# 13_B_T_B_IO.net
KiCad netlist of a schematic drawn in Altium Designer
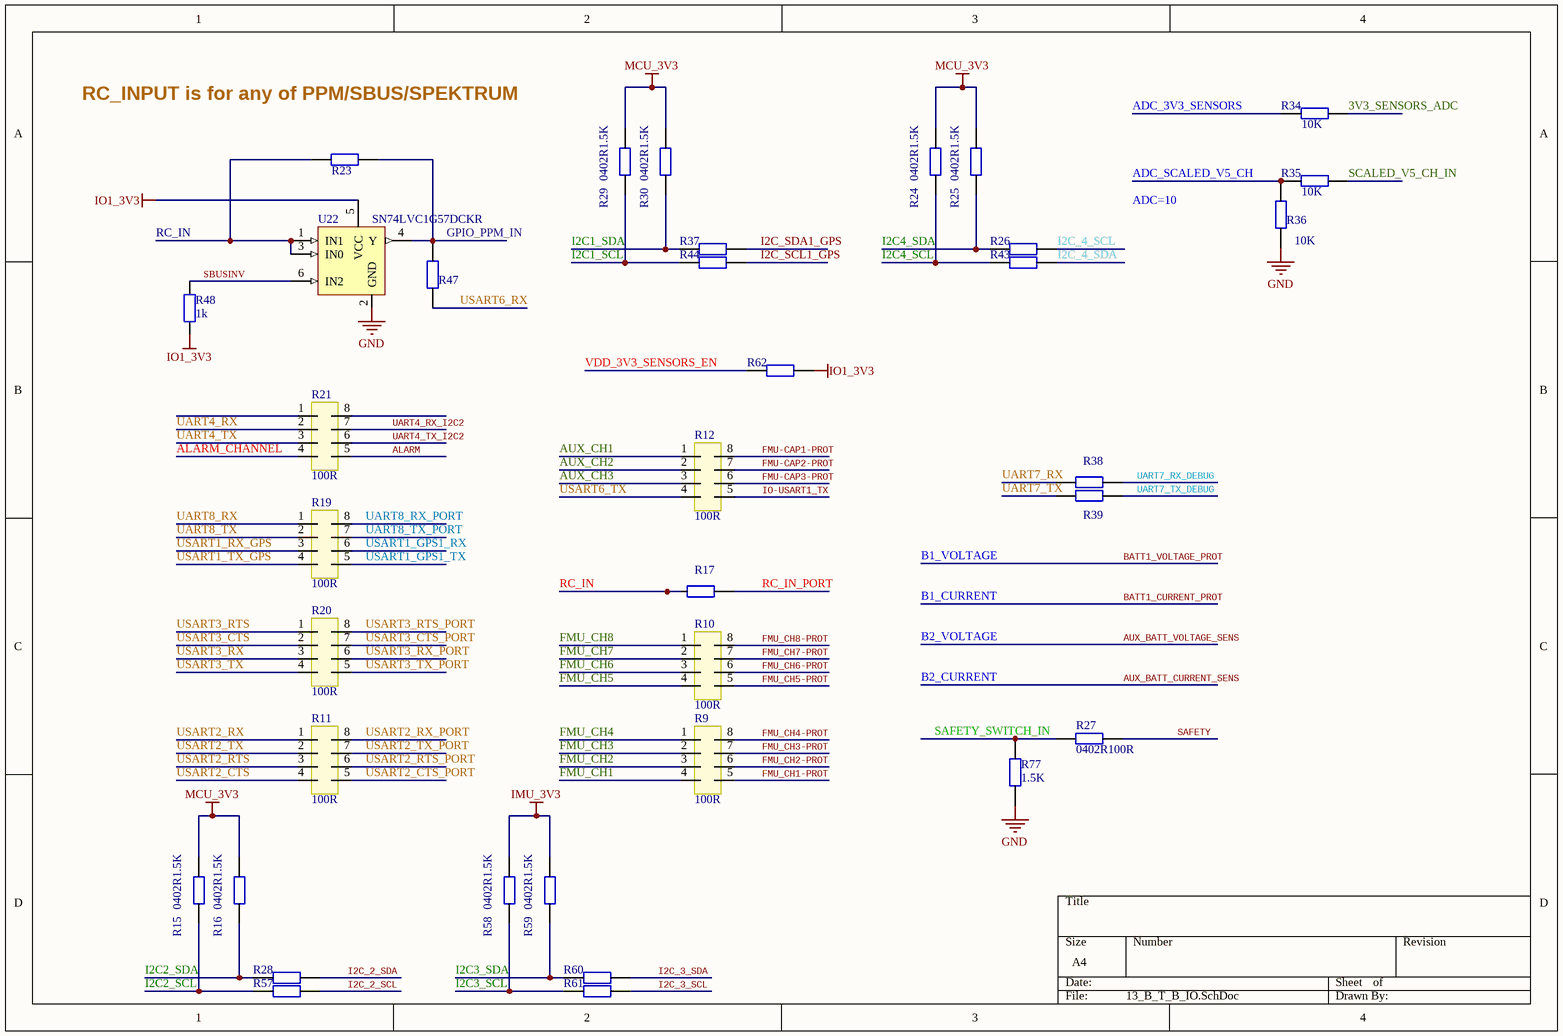
[diagram p0: 13_B_T_B_IO.SchDoc]

(export (version "E")
  (design (tool "Eeschema 10.0.6"))
  (components
    (comp (ref "R9") (value "100R") (footprint "0402_4r") (libsource (lib "CUAV") (part "0402-8R-4R")))
    (comp (ref "R10") (value "100R") (footprint "0402_4r") (libsource (lib "CUAV") (part "0402-8R-4R")))
    (comp (ref "R11") (value "100R") (footprint "0402_4r") (libsource (lib "CUAV") (part "0402-8R-4R")))
    (comp (ref "R12") (value "100R") (footprint "0402_4r") (libsource (lib "CUAV") (part "0402-8R-4R")))
    (comp (ref "R15")
      (value "0402R1.5K")
      (footprint "0402R")
      (description "0402R10K 1%")
      (libsource (lib "CUAV") (part "0402R10K"))
    )
    (comp (ref "R16")
      (value "0402R1.5K")
      (footprint "0402R")
      (description "0402R10K 1%")
      (libsource (lib "CUAV") (part "0402R10K"))
    )
    (comp (ref "R17")
      (value "0402R100R")
      (footprint "0402R")
      (description "0402R100R 1%")
      (libsource (lib "CUAV") (part "0402R100R"))
    )
    (comp (ref "R19") (value "100R") (footprint "0402_4r") (libsource (lib "CUAV") (part "0402-8R-4R")))
    (comp (ref "R20") (value "100R") (footprint "0402_4r") (libsource (lib "CUAV") (part "0402-8R-4R")))
    (comp (ref "R21") (value "100R") (footprint "0402_4r") (libsource (lib "CUAV") (part "0402-8R-4R")))
    (comp (ref "R23")
      (value "100R/NC")
      (footprint "0402R")
      (description "0402R100R 1%")
      (libsource (lib "") (part "0402R100R_1"))
    )
    (comp (ref "R24")
      (value "0402R1.5K")
      (footprint "0402R")
      (description "0402R10K 1%")
      (libsource (lib "CUAV") (part "0402R10K"))
    )
    (comp (ref "R25")
      (value "0402R1.5K")
      (footprint "0402R")
      (description "0402R10K 1%")
      (libsource (lib "CUAV") (part "0402R10K"))
    )
    (comp (ref "R26")
      (value "0402R100R")
      (footprint "0402R")
      (description "0402R100R 1%")
      (libsource (lib "CUAV") (part "0402R100R"))
    )
    (comp (ref "R27")
      (value "0402R100R")
      (footprint "0402R")
      (description "0402R100R 1%")
      (libsource (lib "CUAV") (part "0402R100R"))
    )
    (comp (ref "R28")
      (value "0402R100R")
      (footprint "0402R")
      (description "0402R100R 1%")
      (libsource (lib "CUAV") (part "0402R100R"))
    )
    (comp (ref "R29")
      (value "0402R1.5K")
      (footprint "0402R")
      (description "0402R10K 1%")
      (libsource (lib "CUAV") (part "0402R10K"))
    )
    (comp (ref "R30")
      (value "0402R1.5K")
      (footprint "0402R")
      (description "0402R10K 1%")
      (libsource (lib "CUAV") (part "0402R10K"))
    )
    (comp (ref "R34")
      (value "10K")
      (footprint "0402R")
      (description "0402R100R 1%")
      (libsource (lib "CUAV") (part "0402R100R"))
    )
    (comp (ref "R35")
      (value "10K")
      (footprint "0402R")
      (description "0402R100R 1%")
      (libsource (lib "CUAV") (part "0402R100R"))
    )
    (comp (ref "R36")
      (value "10K")
      (footprint "0402R")
      (description "0402R100R 1%")
      (libsource (lib "") (part "0402R100R_2"))
    )
    (comp (ref "R37")
      (value "0402R100R")
      (footprint "0402R")
      (description "0402R100R 1%")
      (libsource (lib "CUAV") (part "0402R100R"))
    )
    (comp (ref "R38")
      (value "0402R100R")
      (footprint "0402R")
      (description "0402R100R 1%")
      (libsource (lib "CUAV") (part "0402R100R"))
    )
    (comp (ref "R39")
      (value "0402R100R")
      (footprint "0402R")
      (description "0402R100R 1%")
      (libsource (lib "CUAV") (part "0402R100R"))
    )
    (comp (ref "R43")
      (value "0402R100R")
      (footprint "0402R")
      (description "0402R100R 1%")
      (libsource (lib "CUAV") (part "0402R100R"))
    )
    (comp (ref "R44")
      (value "0402R100R")
      (footprint "0402R")
      (description "0402R100R 1%")
      (libsource (lib "CUAV") (part "0402R100R"))
    )
    (comp (ref "R47")
      (value "100R")
      (footprint "0402R")
      (description "0402R100R 1%")
      (libsource (lib "") (part "0402R100R_2"))
    )
    (comp (ref "R48")
      (value "1k")
      (description "Resistor")
      (fields (field (name "PUBLISHER") "Altium Limited"))
      (libsource (lib "Miscellaneous Devices") (part "Res2"))
    )
    (comp (ref "R57")
      (value "0402R100R")
      (footprint "0402R")
      (description "0402R100R 1%")
      (libsource (lib "CUAV") (part "0402R100R"))
    )
    (comp (ref "R58")
      (value "0402R1.5K")
      (footprint "0402R")
      (description "0402R10K 1%")
      (libsource (lib "CUAV") (part "0402R10K"))
    )
    (comp (ref "R59")
      (value "0402R1.5K")
      (footprint "0402R")
      (description "0402R10K 1%")
      (libsource (lib "CUAV") (part "0402R10K"))
    )
    (comp (ref "R60")
      (value "0402R100R")
      (footprint "0402R")
      (description "0402R100R 1%")
      (libsource (lib "CUAV") (part "0402R100R"))
    )
    (comp (ref "R61")
      (value "0402R100R")
      (footprint "0402R")
      (description "0402R100R 1%")
      (libsource (lib "CUAV") (part "0402R100R"))
    )
    (comp (ref "R62")
      (value "10K/NC")
      (footprint "0402R")
      (description "0402R100R 1%")
      (libsource (lib "CUAV") (part "0402R100R"))
    )
    (comp (ref "R77")
      (value "1.5K")
      (footprint "0402R")
      (description "0402R100R 1%")
      (libsource (lib "") (part "0402R100R_2"))
    )
    (comp (ref "U22")
      (value "SN74LVC1G57DCKR")
      (footprint "sot323-6")
      (libsource (lib "My_Altium") (part "74LVC1G57"))
    )
  )
  (nets
    (net (code "1") (name "/3V3_SENSORS_ADC") (class "Default")
      (node (ref "R34") (pin "2") (pintype "passive"))
    )
    (net (code "3") (name "/ADC_3V3_SENSORS") (class "Default")
      (node (ref "R34") (pin "1") (pintype "passive"))
    )
    (net (code "4") (name "/ADC_SCALED_V5_CH") (class "Default")
      (node (ref "R35") (pin "1") (pintype "passive"))
      (node (ref "R36") (pin "2") (pintype "passive"))
    )
    (net (code "5") (name "/ALARM") (class "Default")
      (node (ref "R21") (pin "5") (pinfunction "5_5") (pintype "passive"))
    )
    (net (code "6") (name "/ALARM_CHANNEL") (class "Default")
      (node (ref "R21") (pin "4") (pinfunction "4_4") (pintype "passive"))
    )
    (net (code "9") (name "/AUX_CH1") (class "Default")
      (node (ref "R12") (pin "1") (pinfunction "1_1") (pintype "passive"))
    )
    (net (code "10") (name "/AUX_CH2") (class "Default")
      (node (ref "R12") (pin "2") (pinfunction "2_2") (pintype "passive"))
    )
    (net (code "11") (name "/AUX_CH3") (class "Default")
      (node (ref "R12") (pin "3") (pinfunction "3_3") (pintype "passive"))
    )
    (net (code "14") (name "/FMU-CAP1-PROT") (class "Default")
      (node (ref "R12") (pin "8") (pinfunction "8_8") (pintype "passive"))
    )
    (net (code "15") (name "/FMU-CAP2-PROT") (class "Default")
      (node (ref "R12") (pin "7") (pinfunction "7_7") (pintype "passive"))
    )
    (net (code "16") (name "/FMU-CAP3-PROT") (class "Default")
      (node (ref "R12") (pin "6") (pinfunction "6_6") (pintype "passive"))
    )
    (net (code "17") (name "/FMU_CH1") (class "Default")
      (node (ref "R9") (pin "4") (pinfunction "4_4") (pintype "passive"))
    )
    (net (code "18") (name "/FMU_CH1-PROT") (class "Default")
      (node (ref "R9") (pin "5") (pinfunction "5_5") (pintype "passive"))
    )
    (net (code "19") (name "/FMU_CH2") (class "Default")
      (node (ref "R9") (pin "3") (pinfunction "3_3") (pintype "passive"))
    )
    (net (code "20") (name "/FMU_CH2-PROT") (class "Default")
      (node (ref "R9") (pin "6") (pinfunction "6_6") (pintype "passive"))
    )
    (net (code "21") (name "/FMU_CH3") (class "Default")
      (node (ref "R9") (pin "2") (pinfunction "2_2") (pintype "passive"))
    )
    (net (code "22") (name "/FMU_CH3-PROT") (class "Default")
      (node (ref "R9") (pin "7") (pinfunction "7_7") (pintype "passive"))
    )
    (net (code "23") (name "/FMU_CH4") (class "Default")
      (node (ref "R9") (pin "1") (pinfunction "1_1") (pintype "passive"))
    )
    (net (code "24") (name "/FMU_CH4-PROT") (class "Default")
      (node (ref "R9") (pin "8") (pinfunction "8_8") (pintype "passive"))
    )
    (net (code "25") (name "/FMU_CH5") (class "Default")
      (node (ref "R10") (pin "4") (pinfunction "4_4") (pintype "passive"))
    )
    (net (code "26") (name "/FMU_CH5-PROT") (class "Default")
      (node (ref "R10") (pin "5") (pinfunction "5_5") (pintype "passive"))
    )
    (net (code "27") (name "/FMU_CH6") (class "Default")
      (node (ref "R10") (pin "3") (pinfunction "3_3") (pintype "passive"))
    )
    (net (code "28") (name "/FMU_CH6-PROT") (class "Default")
      (node (ref "R10") (pin "6") (pinfunction "6_6") (pintype "passive"))
    )
    (net (code "29") (name "/FMU_CH7") (class "Default")
      (node (ref "R10") (pin "2") (pinfunction "2_2") (pintype "passive"))
    )
    (net (code "30") (name "/FMU_CH7-PROT") (class "Default")
      (node (ref "R10") (pin "7") (pinfunction "7_7") (pintype "passive"))
    )
    (net (code "31") (name "/FMU_CH8") (class "Default")
      (node (ref "R10") (pin "1") (pinfunction "1_1") (pintype "passive"))
    )
    (net (code "32") (name "/FMU_CH8-PROT") (class "Default")
      (node (ref "R10") (pin "8") (pinfunction "8_8") (pintype "passive"))
    )
    (net (code "33") (name "/GPIO_PPM_IN") (class "Default")
      (node (ref "R23") (pin "1") (pintype "passive"))
      (node (ref "R47") (pin "2") (pintype "passive"))
      (node (ref "U22") (pin "4") (pinfunction "Y_4") (pintype "output"))
    )
    (net (code "34") (name "/I2C1_SCL") (class "Default")
      (node (ref "R29") (pin "1") (pintype "passive"))
      (node (ref "R44") (pin "1") (pintype "passive"))
    )
    (net (code "35") (name "/I2C1_SDA") (class "Default")
      (node (ref "R30") (pin "1") (pintype "passive"))
      (node (ref "R37") (pin "1") (pintype "passive"))
    )
    (net (code "36") (name "/I2C2_SCL") (class "Default")
      (node (ref "R15") (pin "1") (pintype "passive"))
      (node (ref "R57") (pin "1") (pintype "passive"))
    )
    (net (code "37") (name "/I2C2_SDA") (class "Default")
      (node (ref "R16") (pin "1") (pintype "passive"))
      (node (ref "R28") (pin "1") (pintype "passive"))
    )
    (net (code "38") (name "/I2C3_SCL") (class "Default")
      (node (ref "R58") (pin "1") (pintype "passive"))
      (node (ref "R61") (pin "1") (pintype "passive"))
    )
    (net (code "39") (name "/I2C3_SDA") (class "Default")
      (node (ref "R59") (pin "1") (pintype "passive"))
      (node (ref "R60") (pin "1") (pintype "passive"))
    )
    (net (code "40") (name "/I2C4_SCL") (class "Default")
      (node (ref "R24") (pin "1") (pintype "passive"))
      (node (ref "R43") (pin "1") (pintype "passive"))
    )
    (net (code "41") (name "/I2C4_SDA") (class "Default")
      (node (ref "R25") (pin "1") (pintype "passive"))
      (node (ref "R26") (pin "1") (pintype "passive"))
    )
    (net (code "42") (name "/I2C_2_SCL") (class "Default") (node (ref "R57") (pin "2") (pintype "passive")))
    (net (code "43") (name "/I2C_2_SDA") (class "Default") (node (ref "R28") (pin "2") (pintype "passive")))
    (net (code "44") (name "/I2C_3_SCL") (class "Default") (node (ref "R61") (pin "2") (pintype "passive")))
    (net (code "45") (name "/I2C_3_SDA") (class "Default") (node (ref "R60") (pin "2") (pintype "passive")))
    (net (code "46") (name "/I2C_4_SCL") (class "Default") (node (ref "R26") (pin "2") (pintype "passive")))
    (net (code "47") (name "/I2C_4_SDA") (class "Default") (node (ref "R43") (pin "2") (pintype "passive")))
    (net (code "48") (name "/I2C_SCL1_GPS") (class "Default")
      (node (ref "R44") (pin "2") (pintype "passive"))
    )
    (net (code "49") (name "/I2C_SDA1_GPS") (class "Default")
      (node (ref "R37") (pin "2") (pintype "passive"))
    )
    (net (code "50") (name "/IO-USART1_TX") (class "Default")
      (node (ref "R12") (pin "5") (pinfunction "5_5") (pintype "passive"))
    )
    (net (code "51") (name "/RC_IN") (class "Default")
      (node (ref "R17") (pin "1") (pintype "passive"))
      (node (ref "R23") (pin "2") (pintype "passive"))
      (node (ref "U22") (pin "1") (pinfunction "IN1_1") (pintype "input"))
      (node (ref "U22") (pin "3") (pinfunction "IN0_3") (pintype "input"))
    )
    (net (code "52") (name "/RC_IN_PORT") (class "Default") (node (ref "R17") (pin "2") (pintype "passive")))
    (net (code "53") (name "/SAFETY") (class "Default") (node (ref "R27") (pin "2") (pintype "passive")))
    (net (code "54") (name "/SAFETY_SWITCH_IN") (class "Default")
      (node (ref "R27") (pin "1") (pintype "passive"))
      (node (ref "R77") (pin "2") (pintype "passive"))
    )
    (net (code "55") (name "/SBUSINV") (class "Default")
      (node (ref "R48") (pin "2") (pinfunction "2_2") (pintype "passive"))
      (node (ref "U22") (pin "6") (pinfunction "IN2_6") (pintype "input"))
    )
    (net (code "56") (name "/SCALED_V5_CH_IN") (class "Default")
      (node (ref "R35") (pin "2") (pintype "passive"))
    )
    (net (code "57") (name "/UART4_RX") (class "Default")
      (node (ref "R21") (pin "2") (pinfunction "2_2") (pintype "passive"))
    )
    (net (code "58") (name "/UART4_RX_I2C2") (class "Default")
      (node (ref "R21") (pin "7") (pinfunction "7_7") (pintype "passive"))
    )
    (net (code "59") (name "/UART4_TX") (class "Default")
      (node (ref "R21") (pin "3") (pinfunction "3_3") (pintype "passive"))
    )
    (net (code "60") (name "/UART4_TX_I2C2") (class "Default")
      (node (ref "R21") (pin "6") (pinfunction "6_6") (pintype "passive"))
    )
    (net (code "61") (name "/UART7_RX") (class "Default") (node (ref "R38") (pin "1") (pintype "passive")))
    (net (code "62") (name "/UART7_RX_DEBUG") (class "Default")
      (node (ref "R38") (pin "2") (pintype "passive"))
    )
    (net (code "63") (name "/UART7_TX") (class "Default") (node (ref "R39") (pin "1") (pintype "passive")))
    (net (code "64") (name "/UART7_TX_DEBUG") (class "Default")
      (node (ref "R39") (pin "2") (pintype "passive"))
    )
    (net (code "65") (name "/UART8_RX") (class "Default")
      (node (ref "R19") (pin "1") (pinfunction "1_1") (pintype "passive"))
    )
    (net (code "66") (name "/UART8_RX_PORT") (class "Default")
      (node (ref "R19") (pin "8") (pinfunction "8_8") (pintype "passive"))
    )
    (net (code "67") (name "/UART8_TX") (class "Default")
      (node (ref "R19") (pin "2") (pinfunction "2_2") (pintype "passive"))
    )
    (net (code "68") (name "/UART8_TX_PORT") (class "Default")
      (node (ref "R19") (pin "7") (pinfunction "7_7") (pintype "passive"))
    )
    (net (code "69") (name "/USART1_GPS1_RX") (class "Default")
      (node (ref "R19") (pin "6") (pinfunction "6_6") (pintype "passive"))
    )
    (net (code "70") (name "/USART1_GPS1_TX") (class "Default")
      (node (ref "R19") (pin "5") (pinfunction "5_5") (pintype "passive"))
    )
    (net (code "71") (name "/USART1_RX_GPS") (class "Default")
      (node (ref "R19") (pin "3") (pinfunction "3_3") (pintype "passive"))
    )
    (net (code "72") (name "/USART1_TX_GPS") (class "Default")
      (node (ref "R19") (pin "4") (pinfunction "4_4") (pintype "passive"))
    )
    (net (code "73") (name "/USART2_CTS") (class "Default")
      (node (ref "R11") (pin "4") (pinfunction "4_4") (pintype "passive"))
    )
    (net (code "74") (name "/USART2_CTS_PORT") (class "Default")
      (node (ref "R11") (pin "5") (pinfunction "5_5") (pintype "passive"))
    )
    (net (code "75") (name "/USART2_RTS") (class "Default")
      (node (ref "R11") (pin "3") (pinfunction "3_3") (pintype "passive"))
    )
    (net (code "76") (name "/USART2_RTS_PORT") (class "Default")
      (node (ref "R11") (pin "6") (pinfunction "6_6") (pintype "passive"))
    )
    (net (code "77") (name "/USART2_RX") (class "Default")
      (node (ref "R11") (pin "1") (pinfunction "1_1") (pintype "passive"))
    )
    (net (code "78") (name "/USART2_RX_PORT") (class "Default")
      (node (ref "R11") (pin "8") (pinfunction "8_8") (pintype "passive"))
    )
    (net (code "79") (name "/USART2_TX") (class "Default")
      (node (ref "R11") (pin "2") (pinfunction "2_2") (pintype "passive"))
    )
    (net (code "80") (name "/USART2_TX_PORT") (class "Default")
      (node (ref "R11") (pin "7") (pinfunction "7_7") (pintype "passive"))
    )
    (net (code "81") (name "/USART3_CTS") (class "Default")
      (node (ref "R20") (pin "2") (pinfunction "2_2") (pintype "passive"))
    )
    (net (code "82") (name "/USART3_CTS_PORT") (class "Default")
      (node (ref "R20") (pin "7") (pinfunction "7_7") (pintype "passive"))
    )
    (net (code "83") (name "/USART3_RTS") (class "Default")
      (node (ref "R20") (pin "1") (pinfunction "1_1") (pintype "passive"))
    )
    (net (code "84") (name "/USART3_RTS_PORT") (class "Default")
      (node (ref "R20") (pin "8") (pinfunction "8_8") (pintype "passive"))
    )
    (net (code "85") (name "/USART3_RX") (class "Default")
      (node (ref "R20") (pin "3") (pinfunction "3_3") (pintype "passive"))
    )
    (net (code "86") (name "/USART3_RX_PORT") (class "Default")
      (node (ref "R20") (pin "6") (pinfunction "6_6") (pintype "passive"))
    )
    (net (code "87") (name "/USART3_TX") (class "Default")
      (node (ref "R20") (pin "4") (pinfunction "4_4") (pintype "passive"))
    )
    (net (code "88") (name "/USART3_TX_PORT") (class "Default")
      (node (ref "R20") (pin "5") (pinfunction "5_5") (pintype "passive"))
    )
    (net (code "89") (name "/USART6_RX") (class "Default") (node (ref "R47") (pin "1") (pintype "passive")))
    (net (code "90") (name "/USART6_TX") (class "Default")
      (node (ref "R12") (pin "4") (pinfunction "4_4") (pintype "passive"))
    )
    (net (code "91") (name "/VDD_3V3_SENSORS_EN") (class "Default")
      (node (ref "R62") (pin "1") (pintype "passive"))
    )
    (net (code "92") (name "GND") (class "Default")
      (node (ref "R36") (pin "1") (pintype "passive"))
      (node (ref "R77") (pin "1") (pintype "passive"))
      (node (ref "U22") (pin "2") (pinfunction "GND_2") (pintype "power_in"))
    )
    (net (code "93") (name "IMU_3V3") (class "Default")
      (node (ref "R58") (pin "2") (pintype "passive"))
      (node (ref "R59") (pin "2") (pintype "passive"))
    )
    (net (code "94") (name "IO1_3V3") (class "Default")
      (node (ref "R48") (pin "1") (pinfunction "1_1") (pintype "passive"))
      (node (ref "R62") (pin "2") (pintype "passive"))
      (node (ref "U22") (pin "5") (pinfunction "VCC_5") (pintype "power_in"))
    )
    (net (code "95") (name "MCU_3V3") (class "Default")
      (node (ref "R15") (pin "2") (pintype "passive"))
      (node (ref "R16") (pin "2") (pintype "passive"))
      (node (ref "R24") (pin "2") (pintype "passive"))
      (node (ref "R25") (pin "2") (pintype "passive"))
      (node (ref "R29") (pin "2") (pintype "passive"))
      (node (ref "R30") (pin "2") (pintype "passive"))
    )
    (net (code "96") (name "unconnected-(R21-Pad1)") (class "Default")
      (node (ref "R21") (pin "1") (pinfunction "1_1") (pintype "passive"))
    )
    (net (code "97") (name "unconnected-(R21-Pad8)") (class "Default")
      (node (ref "R21") (pin "8") (pinfunction "8_8") (pintype "passive"))
    )
  )
)
